# INT_LTS.net
KiCad netlist of a schematic drawn in EAGLE
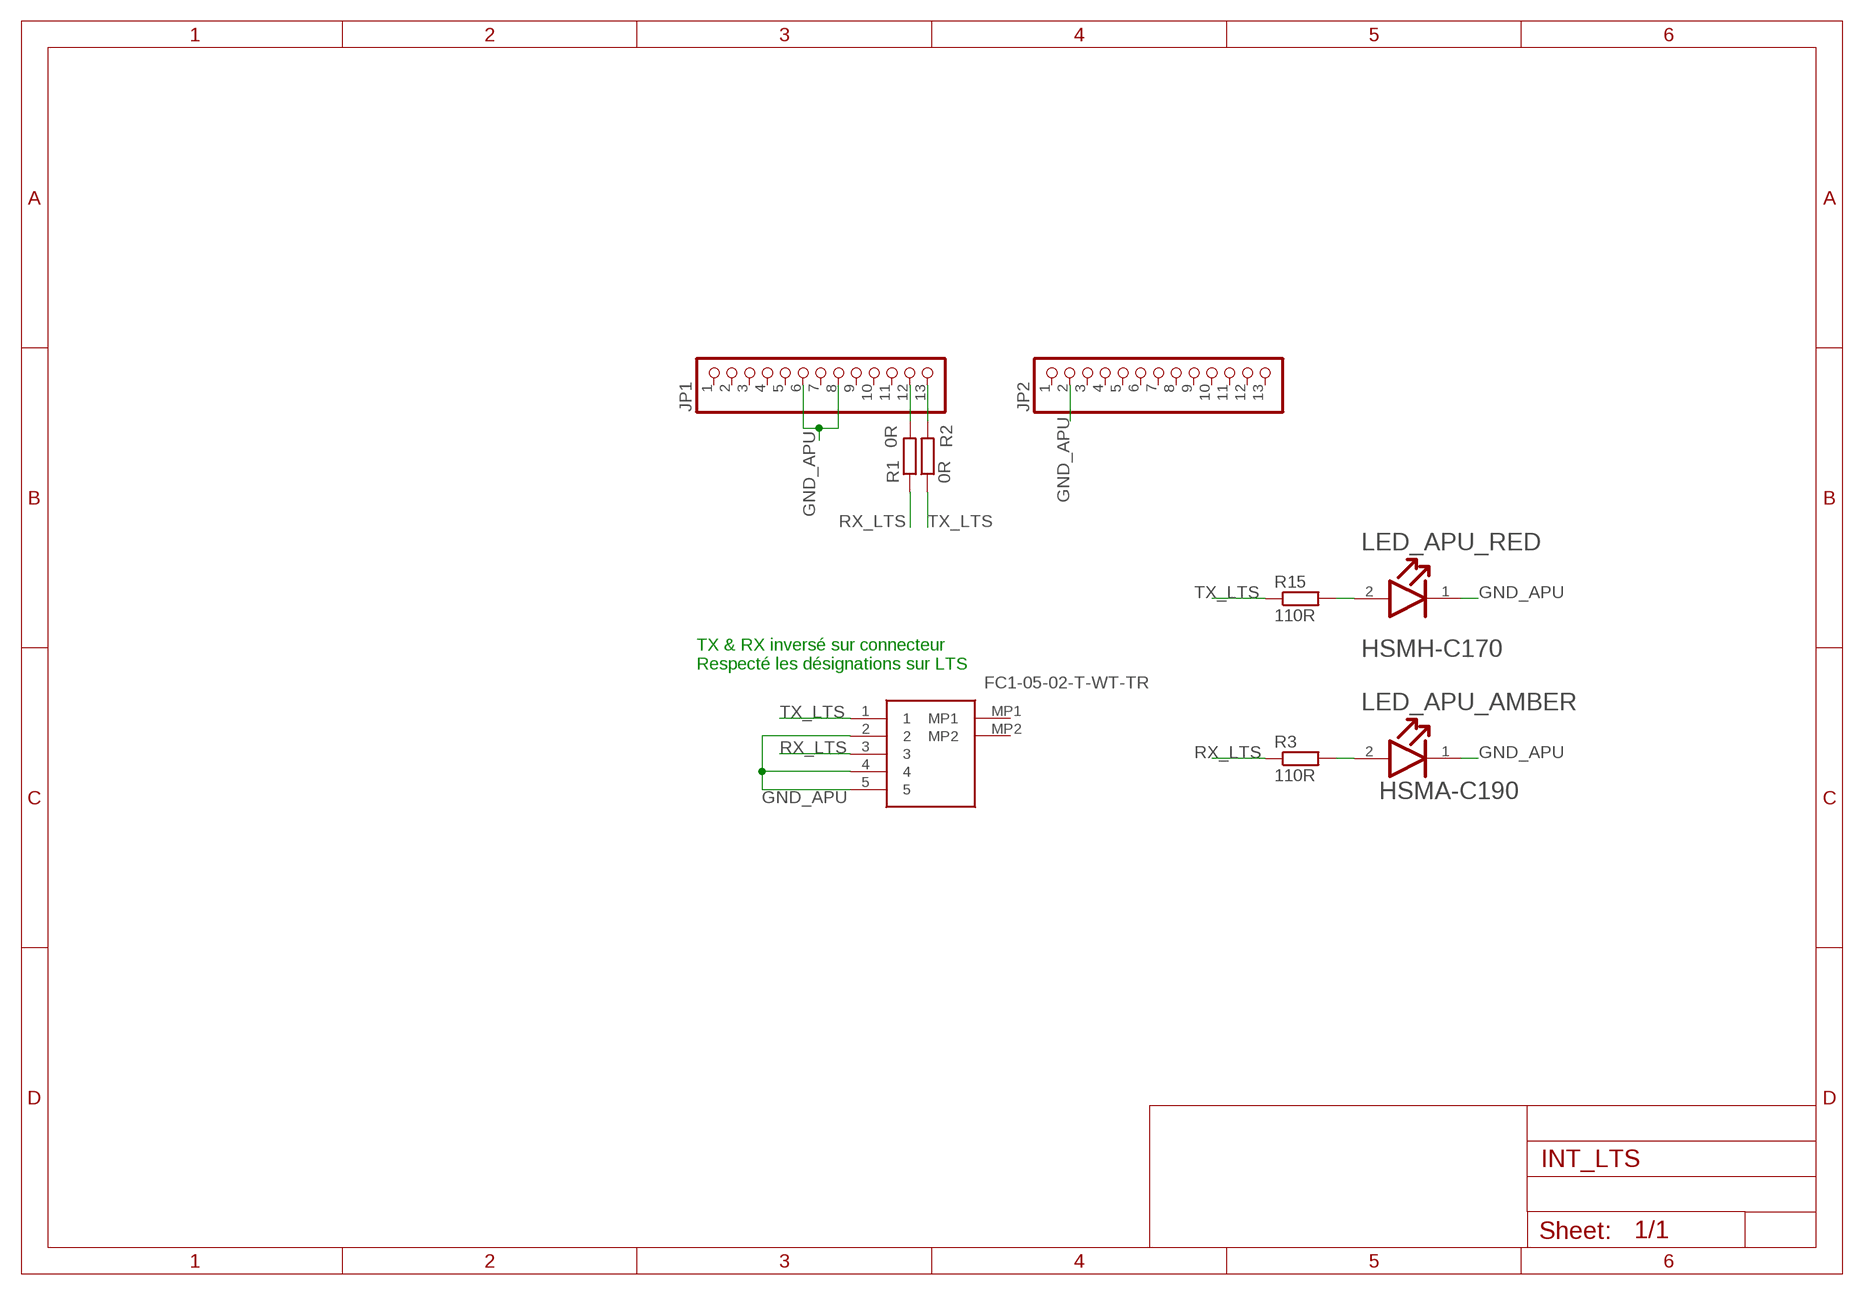
[diagram p0: schematic, sheet 1]

(export (version "E")
  (design (tool "Eeschema 10.0.6"))
  (components
    (comp (ref "J7")
      (value "FC1-05-02-T-WT-TR")
      (footprint "eagle-import:FC10502TWTTR")
      (fields (field (name "MOUSER_PART_NUMBER") "200-FC10502TWTTR"))
      (libsource (lib "eagle-import") (part "FC1-05-02-T-WT-TR"))
    )
    (comp (ref "JP1")
      (value "PINHD-1X13")
      (footprint "eagle-import:1X13")
      (libsource (lib "eagle-import") (part "PINHD-1X13"))
    )
    (comp (ref "JP2")
      (value "PINHD-1X13")
      (footprint "eagle-import:1X13")
      (libsource (lib "eagle-import") (part "PINHD-1X13"))
    )
    (comp (ref "LED_APU_AMBER")
      (value "BROADCOM_HSMA-C190BROADCOM_HSMA-C190_0_0")
      (footprint "eagle-import:BROADCOM_HSMA-C190_0")
      (fields
        (field (name "DIGIKEY_PART_NUMBER") "516-1423-1-ND")
        (field (name "MF") "Broadcom")
        (field (name "MOUSER_PART_NUMBER") "630-HSMA-C190")
      )
      (libsource (lib "eagle-import") (part "BROADCOM_HSMA-C190BROADCOM_HSMA-C190_0_0"))
    )
    (comp (ref "LED_APU_RED")
      (value "BROADCOM_HSMH-C170BROADCOM_HSMH-C170_0_0")
      (footprint "eagle-import:BROADCOM_HSMH-C170_0")
      (fields
        (field (name "DIGIKEY_PART_NUMBER") "516-1427-1-ND")
        (field (name "MF") "Broadcom")
        (field (name "MOUSER_PART_NUMBER") "630-HSMH-C170")
      )
      (libsource (lib "eagle-import") (part "BROADCOM_HSMH-C170BROADCOM_HSMH-C170_0_0"))
    )
    (comp (ref "R1")
      (value "0R")
      (footprint "eagle-import:R0603")
      (libsource (lib "eagle-import") (part "R-EU_R0603"))
    )
    (comp (ref "R2")
      (value "0R")
      (footprint "eagle-import:R0603")
      (libsource (lib "eagle-import") (part "R-EU_R0603"))
    )
    (comp (ref "R3")
      (value "110R")
      (footprint "eagle-import:R0603")
      (libsource (lib "eagle-import") (part "R-EU_R0603"))
    )
    (comp (ref "R15")
      (value "110R")
      (footprint "eagle-import:R0603")
      (libsource (lib "eagle-import") (part "R-EU_R0603"))
    )
  )
  (nets
    (net (code "1") (name "/GND_APU") (class "Default")
      (node (ref "J7") (pin "2") (pinfunction "2_2") (pintype "bidirectional"))
      (node (ref "J7") (pin "4") (pinfunction "4_4") (pintype "bidirectional"))
      (node (ref "J7") (pin "5") (pinfunction "5_5") (pintype "bidirectional"))
      (node (ref "JP1") (pin "6") (pinfunction "6_6") (pintype "passive"))
      (node (ref "JP1") (pin "8") (pinfunction "8_8") (pintype "passive"))
      (node (ref "JP2") (pin "2") (pinfunction "2_2") (pintype "passive"))
      (node (ref "LED_APU_AMBER") (pin "1") (pinfunction "CATHODE_1") (pintype "passive"))
      (node (ref "LED_APU_RED") (pin "1") (pinfunction "CATHODE_1") (pintype "passive"))
    )
    (net (code "2") (name "/RX_LTS") (class "Default")
      (node (ref "J7") (pin "3") (pinfunction "3_3") (pintype "bidirectional"))
      (node (ref "R1") (pin "1") (pinfunction "1_1") (pintype "passive"))
      (node (ref "R3") (pin "1") (pinfunction "1_1") (pintype "passive"))
    )
    (net (code "3") (name "/TX_LTS") (class "Default")
      (node (ref "J7") (pin "1") (pinfunction "1_1") (pintype "bidirectional"))
      (node (ref "R15") (pin "1") (pinfunction "1_1") (pintype "passive"))
      (node (ref "R2") (pin "1") (pinfunction "1_1") (pintype "passive"))
    )
    (net (code "4") (name "Net-(JP1-Pad12)") (class "Default")
      (node (ref "JP1") (pin "12") (pinfunction "12_12") (pintype "passive"))
      (node (ref "R1") (pin "2") (pinfunction "2_2") (pintype "passive"))
    )
    (net (code "5") (name "Net-(JP1-Pad13)") (class "Default")
      (node (ref "JP1") (pin "13") (pinfunction "13_13") (pintype "passive"))
      (node (ref "R2") (pin "2") (pinfunction "2_2") (pintype "passive"))
    )
    (net (code "6") (name "Net-(LED_APU_AMBER-ANODE)") (class "Default")
      (node (ref "LED_APU_AMBER") (pin "2") (pinfunction "ANODE_2") (pintype "passive"))
      (node (ref "R3") (pin "2") (pinfunction "2_2") (pintype "passive"))
    )
    (net (code "7") (name "Net-(LED_APU_RED-ANODE)") (class "Default")
      (node (ref "LED_APU_RED") (pin "2") (pinfunction "ANODE_2") (pintype "passive"))
      (node (ref "R15") (pin "2") (pinfunction "2_2") (pintype "passive"))
    )
    (net (code "8") (name "unconnected-(J7-PadMP1)") (class "Default")
      (node (ref "J7") (pin "MP1") (pinfunction "MP1_MP1") (pintype "bidirectional"))
    )
    (net (code "9") (name "unconnected-(J7-PadMP2)") (class "Default")
      (node (ref "J7") (pin "MP2") (pinfunction "MP2_MP2") (pintype "bidirectional"))
    )
    (net (code "10") (name "unconnected-(JP1-Pad1)") (class "Default")
      (node (ref "JP1") (pin "1") (pinfunction "1_1") (pintype "passive"))
    )
    (net (code "11") (name "unconnected-(JP1-Pad2)") (class "Default")
      (node (ref "JP1") (pin "2") (pinfunction "2_2") (pintype "passive"))
    )
    (net (code "12") (name "unconnected-(JP1-Pad3)") (class "Default")
      (node (ref "JP1") (pin "3") (pinfunction "3_3") (pintype "passive"))
    )
    (net (code "13") (name "unconnected-(JP1-Pad4)") (class "Default")
      (node (ref "JP1") (pin "4") (pinfunction "4_4") (pintype "passive"))
    )
    (net (code "14") (name "unconnected-(JP1-Pad5)") (class "Default")
      (node (ref "JP1") (pin "5") (pinfunction "5_5") (pintype "passive"))
    )
    (net (code "15") (name "unconnected-(JP1-Pad7)") (class "Default")
      (node (ref "JP1") (pin "7") (pinfunction "7_7") (pintype "passive"))
    )
    (net (code "16") (name "unconnected-(JP1-Pad9)") (class "Default")
      (node (ref "JP1") (pin "9") (pinfunction "9_9") (pintype "passive"))
    )
    (net (code "17") (name "unconnected-(JP1-Pad10)") (class "Default")
      (node (ref "JP1") (pin "10") (pinfunction "10_10") (pintype "passive"))
    )
    (net (code "18") (name "unconnected-(JP1-Pad11)") (class "Default")
      (node (ref "JP1") (pin "11") (pinfunction "11_11") (pintype "passive"))
    )
    (net (code "19") (name "unconnected-(JP2-Pad1)") (class "Default")
      (node (ref "JP2") (pin "1") (pinfunction "1_1") (pintype "passive"))
    )
    (net (code "20") (name "unconnected-(JP2-Pad3)") (class "Default")
      (node (ref "JP2") (pin "3") (pinfunction "3_3") (pintype "passive"))
    )
    (net (code "21") (name "unconnected-(JP2-Pad4)") (class "Default")
      (node (ref "JP2") (pin "4") (pinfunction "4_4") (pintype "passive"))
    )
    (net (code "22") (name "unconnected-(JP2-Pad5)") (class "Default")
      (node (ref "JP2") (pin "5") (pinfunction "5_5") (pintype "passive"))
    )
    (net (code "23") (name "unconnected-(JP2-Pad6)") (class "Default")
      (node (ref "JP2") (pin "6") (pinfunction "6_6") (pintype "passive"))
    )
    (net (code "24") (name "unconnected-(JP2-Pad7)") (class "Default")
      (node (ref "JP2") (pin "7") (pinfunction "7_7") (pintype "passive"))
    )
    (net (code "25") (name "unconnected-(JP2-Pad8)") (class "Default")
      (node (ref "JP2") (pin "8") (pinfunction "8_8") (pintype "passive"))
    )
    (net (code "26") (name "unconnected-(JP2-Pad9)") (class "Default")
      (node (ref "JP2") (pin "9") (pinfunction "9_9") (pintype "passive"))
    )
    (net (code "27") (name "unconnected-(JP2-Pad10)") (class "Default")
      (node (ref "JP2") (pin "10") (pinfunction "10_10") (pintype "passive"))
    )
    (net (code "28") (name "unconnected-(JP2-Pad11)") (class "Default")
      (node (ref "JP2") (pin "11") (pinfunction "11_11") (pintype "passive"))
    )
    (net (code "29") (name "unconnected-(JP2-Pad12)") (class "Default")
      (node (ref "JP2") (pin "12") (pinfunction "12_12") (pintype "passive"))
    )
    (net (code "30") (name "unconnected-(JP2-Pad13)") (class "Default")
      (node (ref "JP2") (pin "13") (pinfunction "13_13") (pintype "passive"))
    )
  )
)
